# Adaptive_Cable_Equalizer.net
KiCad netlist of a schematic drawn in EAGLE
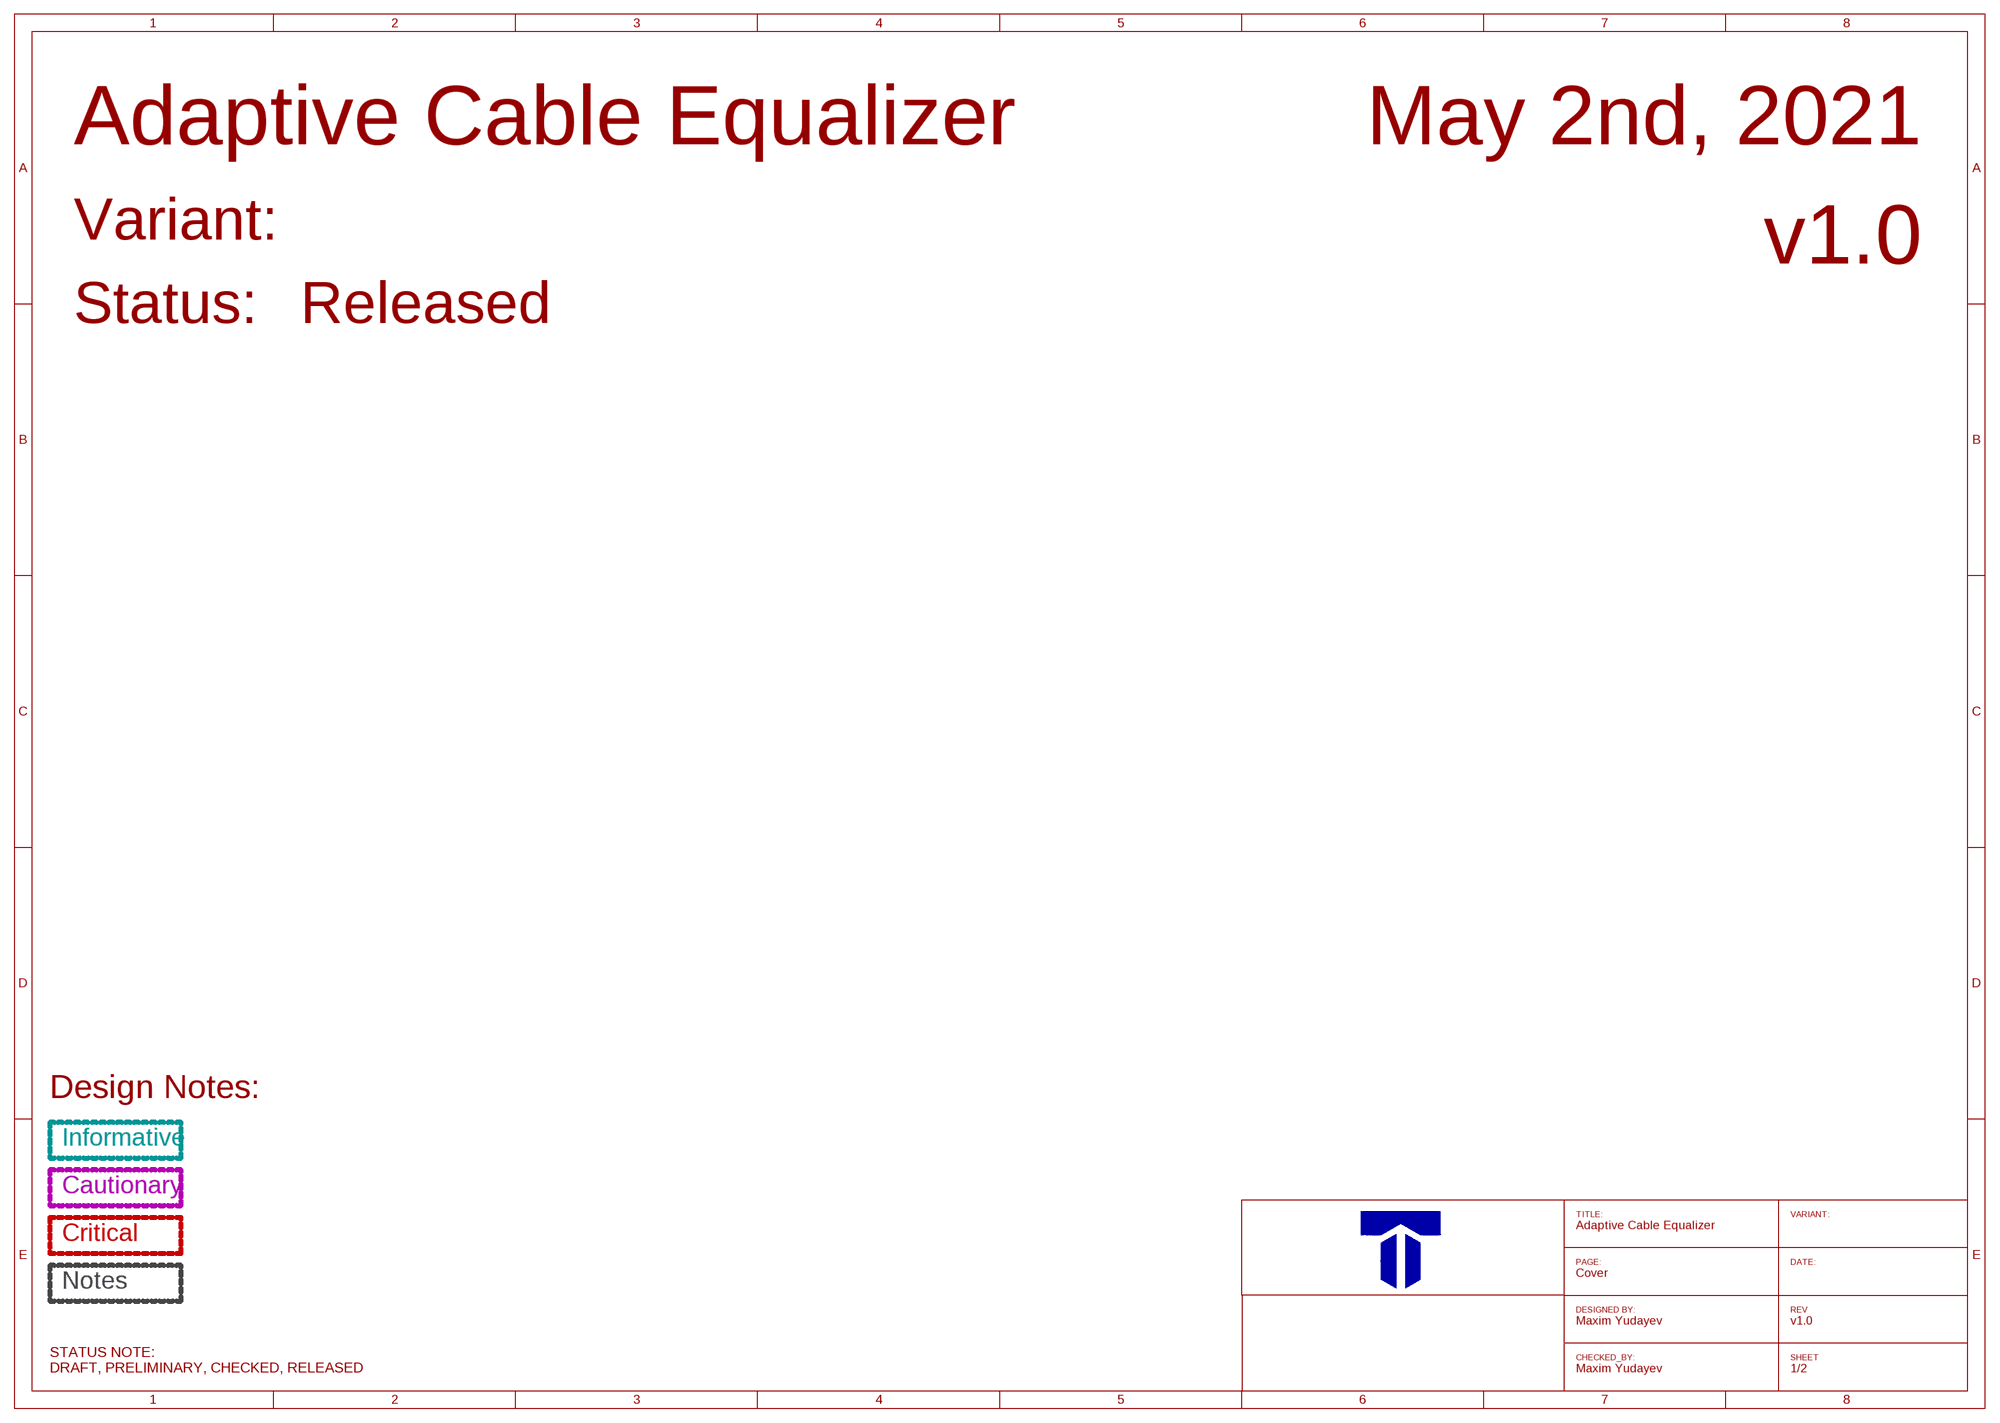
[diagram p0: schematic, sheet 1]
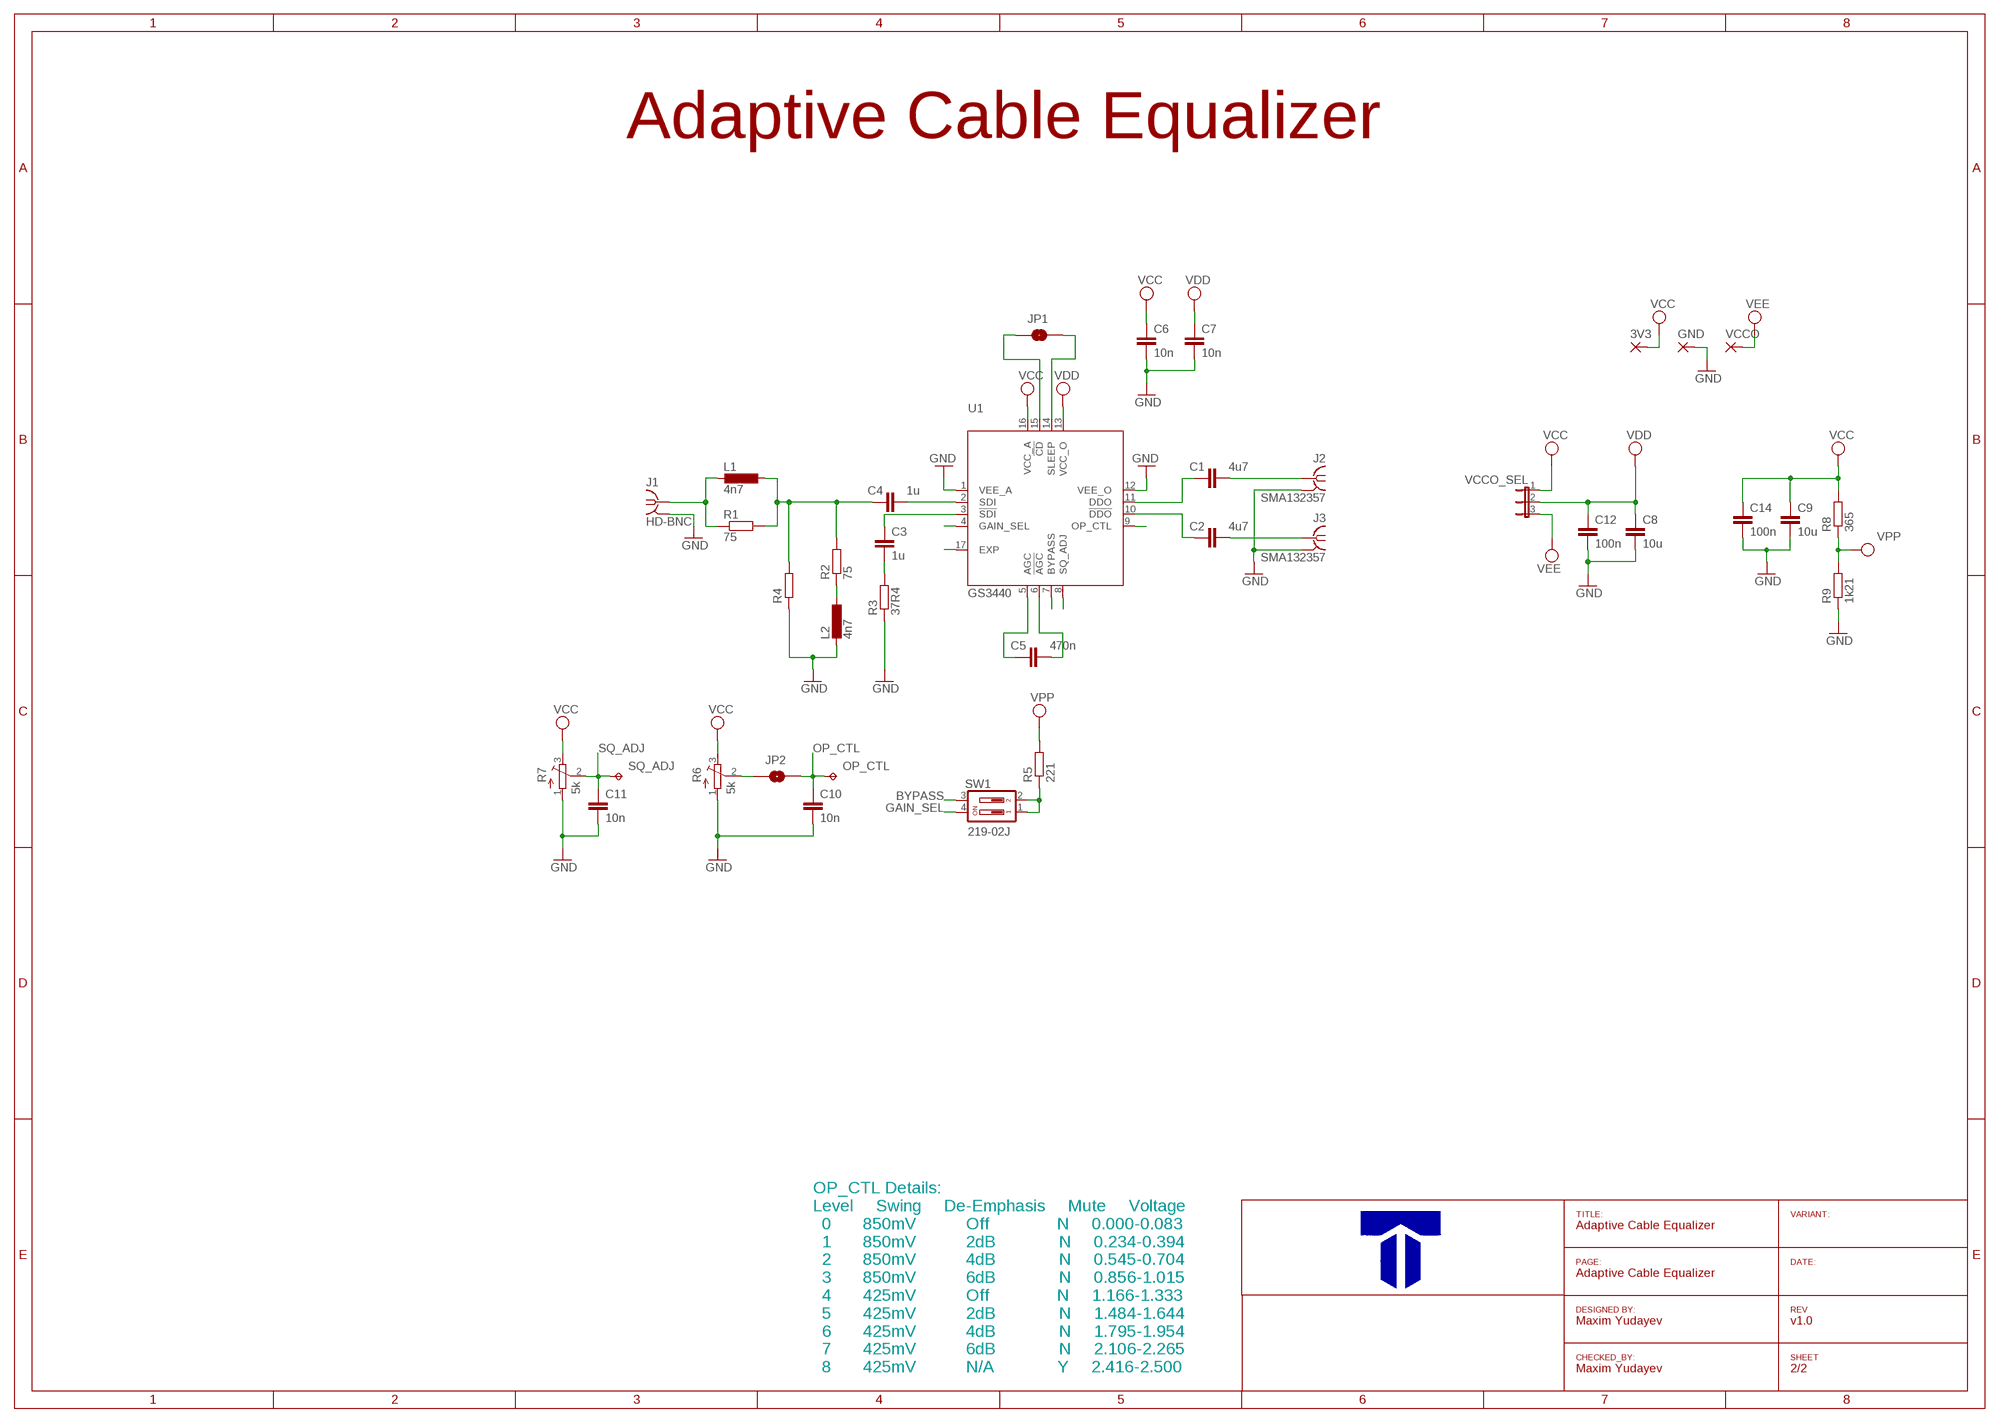
[diagram p1: schematic, sheet 2]

(export (version "E")
  (design (tool "Eeschema 10.0.6"))
  (components
    (comp (ref "3V3")
      (value "TAB_37800568(MSTIN)")
      (footprint "eagle-import:HOLE_1-3")
      (libsource (lib "eagle-import") (part "TAB_37800568(MSTIN)"))
    )
    (comp (ref "C1")
      (value "4u7")
      (footprint "eagle-import:0402")
      (libsource (lib "eagle-import") (part "C0402"))
    )
    (comp (ref "C2")
      (value "4u7")
      (footprint "eagle-import:0402")
      (libsource (lib "eagle-import") (part "C0402"))
    )
    (comp (ref "C3")
      (value "1u")
      (footprint "eagle-import:0402")
      (libsource (lib "eagle-import") (part "C0402"))
    )
    (comp (ref "C4")
      (value "1u")
      (footprint "eagle-import:0402")
      (libsource (lib "eagle-import") (part "C0402"))
    )
    (comp (ref "C5")
      (value "470n")
      (footprint "eagle-import:0402")
      (libsource (lib "eagle-import") (part "C0402"))
    )
    (comp (ref "C6")
      (value "10n")
      (footprint "eagle-import:0402")
      (libsource (lib "eagle-import") (part "C0402"))
    )
    (comp (ref "C7")
      (value "10n")
      (footprint "eagle-import:0402")
      (libsource (lib "eagle-import") (part "C0402"))
    )
    (comp (ref "C8")
      (value "10u")
      (footprint "eagle-import:C0805K")
      (libsource (lib "eagle-import") (part "C-EUC0805K"))
    )
    (comp (ref "C9")
      (value "10u")
      (footprint "eagle-import:C0805K")
      (libsource (lib "eagle-import") (part "C-EUC0805K"))
    )
    (comp (ref "C10")
      (value "10n")
      (footprint "eagle-import:0402")
      (libsource (lib "eagle-import") (part "C0402"))
    )
    (comp (ref "C11")
      (value "10n")
      (footprint "eagle-import:0402")
      (libsource (lib "eagle-import") (part "C0402"))
    )
    (comp (ref "C12")
      (value "100n")
      (footprint "eagle-import:0402")
      (libsource (lib "eagle-import") (part "C0402"))
    )
    (comp (ref "C14")
      (value "100n")
      (footprint "eagle-import:0402")
      (libsource (lib "eagle-import") (part "C0402"))
    )
    (comp (ref "GND")
      (value "TAB_37800568(MSTIN)")
      (footprint "eagle-import:HOLE_1-3")
      (libsource (lib "eagle-import") (part "TAB_37800568(MSTIN)"))
    )
    (comp (ref "J1")
      (value "HD-BNC")
      (footprint "eagle-import:034_1018_12G")
      (libsource (lib "eagle-import") (part "HD-BNC"))
    )
    (comp (ref "J2")
      (value "SMA132357")
      (footprint "eagle-import:SMA")
      (libsource (lib "eagle-import") (part "SMA132357"))
    )
    (comp (ref "J3")
      (value "SMA132357")
      (footprint "eagle-import:SMA")
      (libsource (lib "eagle-import") (part "SMA132357"))
    )
    (comp (ref "JP1")
      (value "SMD-JUMPER")
      (footprint "eagle-import:SMD-JUMPER")
      (libsource (lib "eagle-import") (part "SMD-JUMPER"))
    )
    (comp (ref "JP2")
      (value "SMD-JUMPER")
      (footprint "eagle-import:SMD-JUMPER")
      (libsource (lib "eagle-import") (part "SMD-JUMPER"))
    )
    (comp (ref "L1")
      (value "4n7")
      (footprint "eagle-import:0402")
      (libsource (lib "eagle-import") (part "L0402"))
    )
    (comp (ref "L2")
      (value "4n7")
      (footprint "eagle-import:0402")
      (libsource (lib "eagle-import") (part "L0402"))
    )
    (comp (ref "OP_CTL")
      (value "TPTP06R")
      (footprint "eagle-import:TP06R")
      (libsource (lib "eagle-import") (part "TPTP06R"))
    )
    (comp (ref "R1")
      (value "75")
      (footprint "eagle-import:0402")
      (libsource (lib "eagle-import") (part "R0402"))
    )
    (comp (ref "R2")
      (value "75")
      (footprint "eagle-import:0402")
      (libsource (lib "eagle-import") (part "R0402"))
    )
    (comp (ref "R3")
      (value "37R4")
      (footprint "eagle-import:0402")
      (libsource (lib "eagle-import") (part "R0402"))
    )
    (comp (ref "R4")
      (value "R0402")
      (footprint "eagle-import:0402")
      (libsource (lib "eagle-import") (part "R0402"))
    )
    (comp (ref "R5")
      (value "221")
      (footprint "eagle-import:0402")
      (libsource (lib "eagle-import") (part "R0402"))
    )
    (comp (ref "R6")
      (value "5k")
      (footprint "eagle-import:3223W")
      (libsource (lib "eagle-import") (part "TRIM_EU-3223W"))
    )
    (comp (ref "R7")
      (value "5k")
      (footprint "eagle-import:3223W")
      (libsource (lib "eagle-import") (part "TRIM_EU-3223W"))
    )
    (comp (ref "R8")
      (value "365")
      (footprint "eagle-import:0402")
      (libsource (lib "eagle-import") (part "R0402"))
    )
    (comp (ref "R9")
      (value "1k21")
      (footprint "eagle-import:0402")
      (libsource (lib "eagle-import") (part "R0402"))
    )
    (comp (ref "SQ_ADJ")
      (value "TPTP06R")
      (footprint "eagle-import:TP06R")
      (libsource (lib "eagle-import") (part "TPTP06R"))
    )
    (comp (ref "SW1")
      (value "219-02J")
      (footprint "eagle-import:CTS-219-02J")
      (libsource (lib "eagle-import") (part "219-02J"))
    )
    (comp (ref "U1")
      (value "GS3440")
      (footprint "eagle-import:QFN65P400X400X90-17T260N")
      (libsource (lib "eagle-import") (part "GS3440"))
    )
    (comp (ref "VCCO")
      (value "TAB_37800568(MSTIN)")
      (footprint "eagle-import:HOLE_1-3")
      (libsource (lib "eagle-import") (part "TAB_37800568(MSTIN)"))
    )
    (comp (ref "VCCO_SEL")
      (value "JP2E")
      (footprint "eagle-import:JP2")
      (libsource (lib "eagle-import") (part "JP2E"))
    )
  )
  (nets
    (net (code "1") (name "BYPASS") (class "Default")
      (node (ref "SW1") (pin "3") (pinfunction "3_3") (pintype "passive"))
      (node (ref "U1") (pin "7") (pinfunction "BYPASS_7") (pintype "input"))
    )
    (net (code "2") (name "GAIN_SEL") (class "Default")
      (node (ref "SW1") (pin "4") (pinfunction "4_4") (pintype "passive"))
      (node (ref "U1") (pin "4") (pinfunction "GAIN_SEL_4") (pintype "power_in"))
    )
    (net (code "3") (name "GND") (class "Default")
      (node (ref "C10") (pin "2") (pinfunction "2_2") (pintype "passive"))
      (node (ref "C11") (pin "2") (pinfunction "2_2") (pintype "passive"))
      (node (ref "C12") (pin "2") (pinfunction "2_2") (pintype "passive"))
      (node (ref "C14") (pin "2") (pinfunction "2_2") (pintype "passive"))
      (node (ref "C6") (pin "2") (pinfunction "2_2") (pintype "passive"))
      (node (ref "C7") (pin "2") (pinfunction "2_2") (pintype "passive"))
      (node (ref "C8") (pin "2") (pinfunction "2_2") (pintype "passive"))
      (node (ref "C9") (pin "2") (pinfunction "2_2") (pintype "passive"))
      (node (ref "GND") (pin "P$1") (pinfunction "P_P$1") (pintype "passive"))
      (node (ref "J1") (pin "G@1") (pinfunction "2_G@1") (pintype "passive"))
      (node (ref "J1") (pin "G@2") (pinfunction "2_G@2") (pintype "passive"))
      (node (ref "J1") (pin "G@3") (pinfunction "2_G@3") (pintype "passive"))
      (node (ref "J1") (pin "G@4") (pinfunction "2_G@4") (pintype "passive"))
      (node (ref "J2") (pin "G@1") (pinfunction "2_G@1") (pintype "passive"))
      (node (ref "J2") (pin "G@2") (pinfunction "2_G@2") (pintype "passive"))
      (node (ref "J2") (pin "G@3") (pinfunction "2_G@3") (pintype "passive"))
      (node (ref "J2") (pin "G@4") (pinfunction "2_G@4") (pintype "passive"))
      (node (ref "J3") (pin "G@1") (pinfunction "2_G@1") (pintype "passive"))
      (node (ref "J3") (pin "G@2") (pinfunction "2_G@2") (pintype "passive"))
      (node (ref "J3") (pin "G@3") (pinfunction "2_G@3") (pintype "passive"))
      (node (ref "J3") (pin "G@4") (pinfunction "2_G@4") (pintype "passive"))
      (node (ref "L2") (pin "2") (pinfunction "2_2") (pintype "passive"))
      (node (ref "R3") (pin "1") (pinfunction "1_1") (pintype "passive"))
      (node (ref "R4") (pin "1") (pinfunction "1_1") (pintype "passive"))
      (node (ref "R6") (pin "1") (pinfunction "A_1") (pintype "passive"))
      (node (ref "R7") (pin "1") (pinfunction "A_1") (pintype "passive"))
      (node (ref "R9") (pin "1") (pinfunction "1_1") (pintype "passive"))
      (node (ref "U1") (pin "1") (pinfunction "VEE_A_1") (pintype "power_in"))
      (node (ref "U1") (pin "12") (pinfunction "VEE_O_12") (pintype "power_in"))
      (node (ref "U1") (pin "17") (pinfunction "EXP_17") (pintype "power_in"))
    )
    (net (code "4") (name "Net-(C1-Pad2)") (class "Default")
      (node (ref "C1") (pin "2") (pinfunction "2_2") (pintype "passive"))
      (node (ref "J2") (pin "1") (pinfunction "1_1") (pintype "passive"))
    )
    (net (code "5") (name "Net-(C2-Pad2)") (class "Default")
      (node (ref "C2") (pin "2") (pinfunction "2_2") (pintype "passive"))
      (node (ref "J3") (pin "1") (pinfunction "1_1") (pintype "passive"))
    )
    (net (code "6") (name "Net-(C3-Pad2)") (class "Default")
      (node (ref "C3") (pin "2") (pinfunction "2_2") (pintype "passive"))
      (node (ref "R3") (pin "2") (pinfunction "2_2") (pintype "passive"))
    )
    (net (code "7") (name "Net-(C4-Pad1)") (class "Default")
      (node (ref "C4") (pin "1") (pinfunction "1_1") (pintype "passive"))
      (node (ref "L1") (pin "1") (pinfunction "1_1") (pintype "passive"))
      (node (ref "R1") (pin "2") (pinfunction "2_2") (pintype "passive"))
      (node (ref "R2") (pin "2") (pinfunction "2_2") (pintype "passive"))
      (node (ref "R4") (pin "2") (pinfunction "2_2") (pintype "passive"))
    )
    (net (code "8") (name "Net-(J1-1)") (class "Default")
      (node (ref "J1") (pin "P$1") (pinfunction "1_P$1") (pintype "passive"))
      (node (ref "L1") (pin "2") (pinfunction "2_2") (pintype "passive"))
      (node (ref "R1") (pin "1") (pinfunction "1_1") (pintype "passive"))
    )
    (net (code "9") (name "Net-(JP1-1)") (class "Default")
      (node (ref "JP1") (pin "P$1") (pinfunction "1_P$1") (pintype "passive"))
      (node (ref "U1") (pin "15") (pinfunction "~{CD}_15") (pintype "output"))
    )
    (net (code "10") (name "Net-(JP1-2)") (class "Default")
      (node (ref "JP1") (pin "P$2") (pinfunction "2_P$2") (pintype "passive"))
      (node (ref "U1") (pin "14") (pinfunction "SLEEP_14") (pintype "input"))
    )
    (net (code "11") (name "Net-(JP2-1)") (class "Default")
      (node (ref "JP2") (pin "P$1") (pinfunction "1_P$1") (pintype "passive"))
      (node (ref "R6") (pin "2") (pinfunction "S_2") (pintype "passive"))
    )
    (net (code "12") (name "Net-(L2-Pad1)") (class "Default")
      (node (ref "L2") (pin "1") (pinfunction "1_1") (pintype "passive"))
      (node (ref "R2") (pin "1") (pinfunction "1_1") (pintype "passive"))
    )
    (net (code "13") (name "Net-(R5-Pad1)") (class "Default")
      (node (ref "R5") (pin "1") (pinfunction "1_1") (pintype "passive"))
      (node (ref "SW1") (pin "1") (pinfunction "1_1") (pintype "passive"))
      (node (ref "SW1") (pin "2") (pinfunction "2_2") (pintype "passive"))
    )
    (net (code "14") (name "Net-(U1-AGC)") (class "Default")
      (node (ref "C5") (pin "1") (pinfunction "1_1") (pintype "passive"))
      (node (ref "U1") (pin "5") (pinfunction "AGC_5") (pintype "passive"))
    )
    (net (code "15") (name "Net-(U1-DDO)") (class "Default")
      (node (ref "C1") (pin "1") (pinfunction "1_1") (pintype "passive"))
      (node (ref "U1") (pin "11") (pinfunction "DDO_11") (pintype "output"))
    )
    (net (code "16") (name "Net-(U1-SDI)") (class "Default")
      (node (ref "C4") (pin "2") (pinfunction "2_2") (pintype "passive"))
      (node (ref "U1") (pin "2") (pinfunction "SDI_2") (pintype "input"))
    )
    (net (code "17") (name "Net-(U1-~{AGC})") (class "Default")
      (node (ref "C5") (pin "2") (pinfunction "2_2") (pintype "passive"))
      (node (ref "U1") (pin "6") (pinfunction "~{AGC}_6") (pintype "passive"))
    )
    (net (code "18") (name "Net-(U1-~{DDO})") (class "Default")
      (node (ref "C2") (pin "1") (pinfunction "1_1") (pintype "passive"))
      (node (ref "U1") (pin "10") (pinfunction "~{DDO}_10") (pintype "output"))
    )
    (net (code "19") (name "Net-(U1-~{SDI})") (class "Default")
      (node (ref "C3") (pin "1") (pinfunction "1_1") (pintype "passive"))
      (node (ref "U1") (pin "3") (pinfunction "~{SDI}_3") (pintype "input"))
    )
    (net (code "20") (name "OP_CTL") (class "Default")
      (node (ref "C10") (pin "1") (pinfunction "1_1") (pintype "passive"))
      (node (ref "JP2") (pin "P$2") (pinfunction "2_P$2") (pintype "passive"))
      (node (ref "OP_CTL") (pin "TP") (pinfunction "TP_TP") (pintype "input"))
      (node (ref "U1") (pin "9") (pinfunction "OP_CTL_9") (pintype "power_in"))
    )
    (net (code "21") (name "SQ_ADJ") (class "Default")
      (node (ref "C11") (pin "1") (pinfunction "1_1") (pintype "passive"))
      (node (ref "R7") (pin "2") (pinfunction "S_2") (pintype "passive"))
      (node (ref "SQ_ADJ") (pin "TP") (pinfunction "TP_TP") (pintype "input"))
      (node (ref "U1") (pin "8") (pinfunction "SQ_ADJ_8") (pintype "input"))
    )
    (net (code "22") (name "VCC") (class "Default")
      (node (ref "3V3") (pin "P$1") (pinfunction "P_P$1") (pintype "passive"))
      (node (ref "C14") (pin "1") (pinfunction "1_1") (pintype "passive"))
      (node (ref "C6") (pin "1") (pinfunction "1_1") (pintype "passive"))
      (node (ref "C9") (pin "1") (pinfunction "1_1") (pintype "passive"))
      (node (ref "R6") (pin "3") (pinfunction "E_3") (pintype "passive"))
      (node (ref "R7") (pin "3") (pinfunction "E_3") (pintype "passive"))
      (node (ref "R8") (pin "2") (pinfunction "2_2") (pintype "passive"))
      (node (ref "U1") (pin "16") (pinfunction "VCC_A_16") (pintype "power_in"))
      (node (ref "VCCO_SEL") (pin "1") (pinfunction "1_1") (pintype "passive"))
    )
    (net (code "23") (name "VDD") (class "Default")
      (node (ref "C12") (pin "1") (pinfunction "1_1") (pintype "passive"))
      (node (ref "C7") (pin "1") (pinfunction "1_1") (pintype "passive"))
      (node (ref "C8") (pin "1") (pinfunction "1_1") (pintype "passive"))
      (node (ref "U1") (pin "13") (pinfunction "VCC_O_13") (pintype "power_in"))
      (node (ref "VCCO_SEL") (pin "2") (pinfunction "2_2") (pintype "passive"))
    )
    (net (code "24") (name "VEE") (class "Default")
      (node (ref "VCCO") (pin "P$1") (pinfunction "P_P$1") (pintype "passive"))
      (node (ref "VCCO_SEL") (pin "3") (pinfunction "3_3") (pintype "passive"))
    )
    (net (code "25") (name "VPP") (class "Default")
      (node (ref "R5") (pin "2") (pinfunction "2_2") (pintype "passive"))
      (node (ref "R8") (pin "1") (pinfunction "1_1") (pintype "passive"))
      (node (ref "R9") (pin "2") (pinfunction "2_2") (pintype "passive"))
    )
  )
)
